# Mainboard.net
KiCad netlist of a schematic drawn in EAGLE
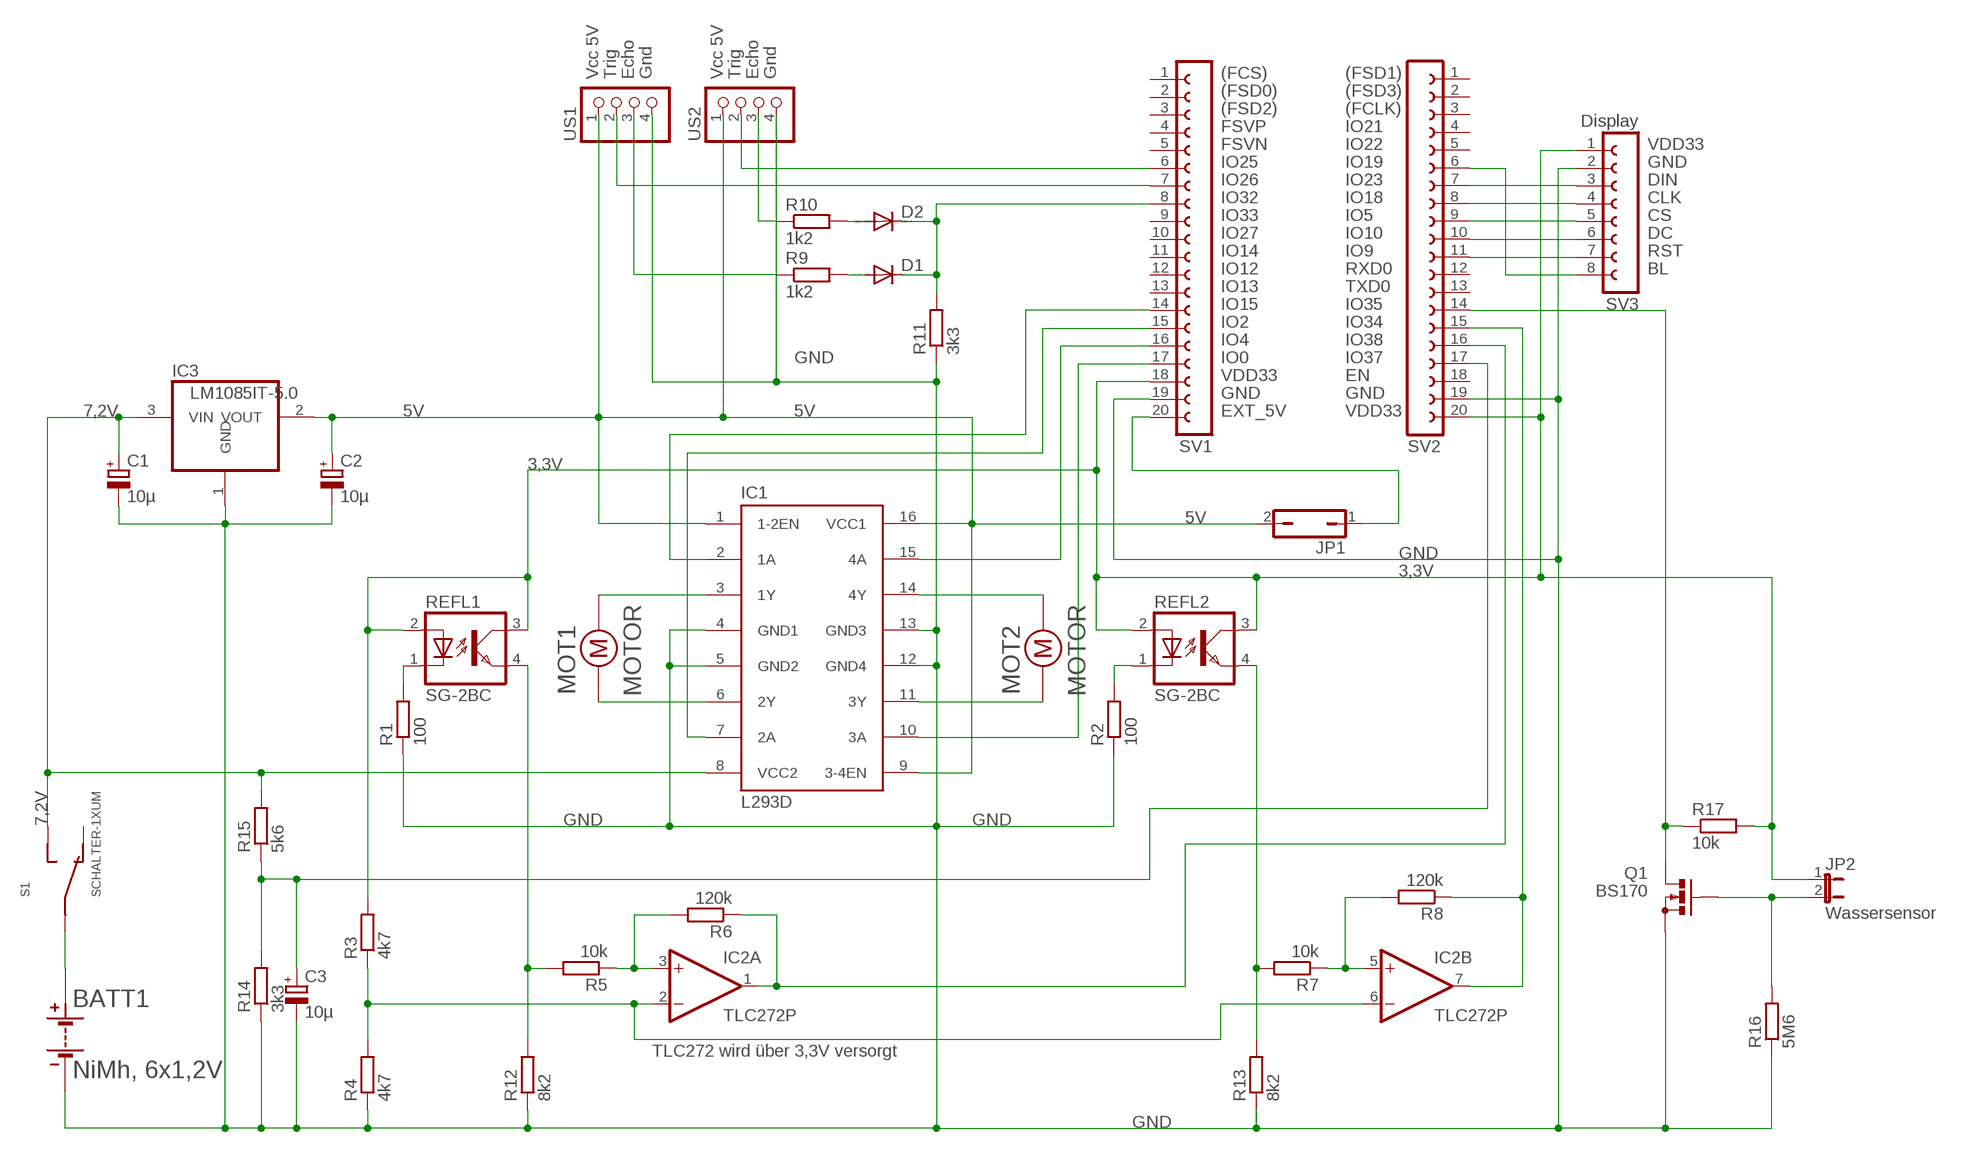
[diagram p0: schematic, sheet 1]

(export (version "E")
  (design (tool "Eeschema 10.0.6"))
  (components
    (comp (ref "BATT1")
      (value "NiMh, 6x1,2V")
      (footprint "eagle-import:DUMMY2P")
      (libsource (lib "eagle-import") (part "BATTERIEN"))
    )
    (comp (ref "C1")
      (value "10µ")
      (footprint "eagle-import:E3,5-10")
      (libsource (lib "eagle-import") (part "CPOL-EUE3.5-10"))
    )
    (comp (ref "C2")
      (value "10µ")
      (footprint "eagle-import:E3,5-10")
      (libsource (lib "eagle-import") (part "CPOL-EUE3.5-10"))
    )
    (comp (ref "C3")
      (value "10µ")
      (footprint "eagle-import:E3,5-10")
      (libsource (lib "eagle-import") (part "CPOL-EUE3.5-10"))
    )
    (comp (ref "D1")
      (value "1N4148DO35-10")
      (footprint "eagle-import:DO35-10")
      (libsource (lib "eagle-import") (part "1N4148DO35-10"))
    )
    (comp (ref "D2")
      (value "1N4148DO35-10")
      (footprint "eagle-import:DO35-10")
      (libsource (lib "eagle-import") (part "1N4148DO35-10"))
    )
    (comp (ref "IC1")
      (value "L293D")
      (footprint "eagle-import:DIL16")
      (libsource (lib "eagle-import") (part "L293D"))
    )
    (comp (ref "IC2")
      (value "TLC272P")
      (footprint "eagle-import:DIL08")
      (libsource (lib "eagle-import") (part "TLC272P"))
    )
    (comp (ref "IC3")
      (value "LM1085IT-5.0")
      (footprint "eagle-import:DD-3")
      (fields (field (name "MF") "TEXAS INSTRUMENTS") (field (name "MPN") "REG1117FAKTTT"))
      (libsource (lib "eagle-import") (part "REG1117F"))
    )
    (comp (ref "JP1")
      (value "JP1Q")
      (footprint "eagle-import:JP1")
      (libsource (lib "eagle-import") (part "JP1Q"))
    )
    (comp (ref "JP2")
      (value "Wassersensor")
      (footprint "eagle-import:JP1")
      (libsource (lib "eagle-import") (part "JP1E"))
    )
    (comp (ref "MOT1")
      (value "MOTOR")
      (footprint "eagle-import:DUMMY2P")
      (libsource (lib "eagle-import") (part "MOTOR"))
    )
    (comp (ref "MOT2")
      (value "MOTOR")
      (footprint "eagle-import:DUMMY2P")
      (libsource (lib "eagle-import") (part "MOTOR"))
    )
    (comp (ref "Q1")
      (value "BS170")
      (footprint "eagle-import:SOT54E")
      (libsource (lib "eagle-import") (part "BS170"))
    )
    (comp (ref "R1")
      (value "100")
      (footprint "eagle-import:RDH_15")
      (libsource (lib "eagle-import") (part "R-EU_RDH/15"))
    )
    (comp (ref "R2")
      (value "100")
      (footprint "eagle-import:RDH_15")
      (libsource (lib "eagle-import") (part "R-EU_RDH/15"))
    )
    (comp (ref "R3")
      (value "4k7")
      (footprint "eagle-import:RDH_15")
      (libsource (lib "eagle-import") (part "R-EU_RDH/15"))
    )
    (comp (ref "R4")
      (value "4k7")
      (footprint "eagle-import:RDH_15")
      (libsource (lib "eagle-import") (part "R-EU_RDH/15"))
    )
    (comp (ref "R5")
      (value "10k")
      (footprint "eagle-import:RDH_15")
      (libsource (lib "eagle-import") (part "R-EU_RDH/15"))
    )
    (comp (ref "R6")
      (value "120k")
      (footprint "eagle-import:RDH_15")
      (libsource (lib "eagle-import") (part "R-EU_RDH/15"))
    )
    (comp (ref "R7")
      (value "10k")
      (footprint "eagle-import:RDH_15")
      (libsource (lib "eagle-import") (part "R-EU_RDH/15"))
    )
    (comp (ref "R8")
      (value "120k")
      (footprint "eagle-import:RDH_15")
      (libsource (lib "eagle-import") (part "R-EU_RDH/15"))
    )
    (comp (ref "R9")
      (value "1k2")
      (footprint "eagle-import:RDH_15")
      (libsource (lib "eagle-import") (part "R-EU_RDH/15"))
    )
    (comp (ref "R10")
      (value "1k2")
      (footprint "eagle-import:RDH_15")
      (libsource (lib "eagle-import") (part "R-EU_RDH/15"))
    )
    (comp (ref "R11")
      (value "3k3")
      (footprint "eagle-import:RDH_15")
      (libsource (lib "eagle-import") (part "R-EU_RDH/15"))
    )
    (comp (ref "R12")
      (value "8k2")
      (footprint "eagle-import:RDH_15")
      (libsource (lib "eagle-import") (part "R-EU_RDH/15"))
    )
    (comp (ref "R13")
      (value "8k2")
      (footprint "eagle-import:RDH_15")
      (libsource (lib "eagle-import") (part "R-EU_RDH/15"))
    )
    (comp (ref "R14")
      (value "3k3")
      (footprint "eagle-import:RDH_15")
      (libsource (lib "eagle-import") (part "R-EU_RDH/15"))
    )
    (comp (ref "R15")
      (value "5k6")
      (footprint "eagle-import:RDH_15")
      (libsource (lib "eagle-import") (part "R-EU_RDH/15"))
    )
    (comp (ref "R16")
      (value "5M6")
      (footprint "eagle-import:RDH_15")
      (libsource (lib "eagle-import") (part "R-EU_RDH/15"))
    )
    (comp (ref "R17")
      (value "10k")
      (footprint "eagle-import:RDH_15")
      (libsource (lib "eagle-import") (part "R-EU_RDH/15"))
    )
    (comp (ref "REFL1")
      (value "SG-2BC")
      (footprint "eagle-import:DIL04")
      (libsource (lib "eagle-import") (part "REFLEXKOPPLERSG-2BC"))
    )
    (comp (ref "REFL2")
      (value "SG-2BC")
      (footprint "eagle-import:DIL04")
      (libsource (lib "eagle-import") (part "REFLEXKOPPLERSG-2BC"))
    )
    (comp (ref "S1")
      (value "SCHALTER-1XUM")
      (footprint "eagle-import:DUMMY3P")
      (libsource (lib "eagle-import") (part "SCHALTER-1XUM"))
    )
    (comp (ref "SV1")
      (value "FE20-1")
      (footprint "eagle-import:FE20")
      (libsource (lib "eagle-import") (part "FE20-1"))
    )
    (comp (ref "SV2")
      (value "FE20-1")
      (footprint "eagle-import:FE20")
      (libsource (lib "eagle-import") (part "FE20-1"))
    )
    (comp (ref "SV3")
      (value "Display")
      (footprint "eagle-import:FE08")
      (libsource (lib "eagle-import") (part "FE08-1"))
    )
    (comp (ref "US1")
      (value "PINHD-1X4")
      (footprint "eagle-import:1X04")
      (libsource (lib "eagle-import") (part "PINHD-1X4"))
    )
    (comp (ref "US2")
      (value "PINHD-1X4")
      (footprint "eagle-import:1X04")
      (libsource (lib "eagle-import") (part "PINHD-1X4"))
    )
  )
  (nets
    (net (code "1") (name "/3,3V") (class "Default")
      (node (ref "JP2") (pin "1") (pinfunction "1_1") (pintype "passive"))
      (node (ref "R17") (pin "2") (pinfunction "2_2") (pintype "passive"))
      (node (ref "R3") (pin "2") (pinfunction "2_2") (pintype "passive"))
      (node (ref "REFL1") (pin "2") (pinfunction "A_2") (pintype "passive"))
      (node (ref "REFL1") (pin "3") (pinfunction "COL_3") (pintype "passive"))
      (node (ref "REFL2") (pin "2") (pinfunction "A_2") (pintype "passive"))
      (node (ref "REFL2") (pin "3") (pinfunction "COL_3") (pintype "passive"))
      (node (ref "SV1") (pin "18") (pinfunction "18_18") (pintype "passive"))
      (node (ref "SV2") (pin "20") (pinfunction "20_20") (pintype "passive"))
      (node (ref "SV3") (pin "1") (pinfunction "1_1") (pintype "passive"))
    )
    (net (code "2") (name "/5V") (class "Default")
      (node (ref "C2") (pin "+") (pinfunction "+_+") (pintype "passive"))
      (node (ref "IC1") (pin "1") (pinfunction "1-2EN_1") (pintype "input"))
      (node (ref "IC1") (pin "16") (pinfunction "VCC1_16") (pintype "power_in"))
      (node (ref "IC1") (pin "9") (pinfunction "3-4EN_9") (pintype "input"))
      (node (ref "IC3") (pin "2") (pinfunction "VOUT_2") (pintype "output"))
      (node (ref "JP1") (pin "2") (pinfunction "2_2") (pintype "passive"))
      (node (ref "US1") (pin "1") (pinfunction "1_1") (pintype "passive"))
      (node (ref "US2") (pin "1") (pinfunction "1_1") (pintype "passive"))
    )
    (net (code "3") (name "/7,2V") (class "Default")
      (node (ref "C1") (pin "+") (pinfunction "+_+") (pintype "passive"))
      (node (ref "IC1") (pin "8") (pinfunction "VCC2_8") (pintype "power_in"))
      (node (ref "IC3") (pin "3") (pinfunction "VIN_3") (pintype "input"))
      (node (ref "R15") (pin "2") (pinfunction "2_2") (pintype "passive"))
      (node (ref "S1") (pin "P$2") (pinfunction "P$2_P$2") (pintype "passive"))
    )
    (net (code "4") (name "/GND") (class "Default")
      (node (ref "BATT1") (pin "P$1") (pinfunction "M_P$1") (pintype "power_in"))
      (node (ref "C1") (pin "-") (pinfunction "-_-") (pintype "passive"))
      (node (ref "C2") (pin "-") (pinfunction "-_-") (pintype "passive"))
      (node (ref "C3") (pin "-") (pinfunction "-_-") (pintype "passive"))
      (node (ref "IC1") (pin "12") (pinfunction "GND4_12") (pintype "power_in"))
      (node (ref "IC1") (pin "13") (pinfunction "GND3_13") (pintype "power_in"))
      (node (ref "IC1") (pin "4") (pinfunction "GND1_4") (pintype "power_in"))
      (node (ref "IC1") (pin "5") (pinfunction "GND2_5") (pintype "power_in"))
      (node (ref "IC3") (pin "1") (pinfunction "GND_1") (pintype "power_in"))
      (node (ref "Q1") (pin "S") (pinfunction "S_S") (pintype "passive"))
      (node (ref "R1") (pin "1") (pinfunction "1_1") (pintype "passive"))
      (node (ref "R11") (pin "1") (pinfunction "1_1") (pintype "passive"))
      (node (ref "R12") (pin "1") (pinfunction "1_1") (pintype "passive"))
      (node (ref "R13") (pin "1") (pinfunction "1_1") (pintype "passive"))
      (node (ref "R14") (pin "1") (pinfunction "1_1") (pintype "passive"))
      (node (ref "R16") (pin "1") (pinfunction "1_1") (pintype "passive"))
      (node (ref "R2") (pin "1") (pinfunction "1_1") (pintype "passive"))
      (node (ref "R4") (pin "1") (pinfunction "1_1") (pintype "passive"))
      (node (ref "SV1") (pin "19") (pinfunction "19_19") (pintype "passive"))
      (node (ref "SV2") (pin "19") (pinfunction "19_19") (pintype "passive"))
      (node (ref "SV3") (pin "2") (pinfunction "2_2") (pintype "passive"))
      (node (ref "US1") (pin "4") (pinfunction "4_4") (pintype "passive"))
      (node (ref "US2") (pin "4") (pinfunction "4_4") (pintype "passive"))
    )
    (net (code "5") (name "Net-(BATT1-P)") (class "Default")
      (node (ref "BATT1") (pin "P$2") (pinfunction "P_P$2") (pintype "power_in"))
      (node (ref "S1") (pin "P$1") (pinfunction "P$1_P$1") (pintype "passive"))
    )
    (net (code "6") (name "Net-(C3-Pad+)") (class "Default")
      (node (ref "C3") (pin "+") (pinfunction "+_+") (pintype "passive"))
      (node (ref "R14") (pin "2") (pinfunction "2_2") (pintype "passive"))
      (node (ref "R15") (pin "1") (pinfunction "1_1") (pintype "passive"))
      (node (ref "SV2") (pin "17") (pinfunction "17_17") (pintype "passive"))
    )
    (net (code "7") (name "Net-(D1-PadA)") (class "Default")
      (node (ref "D1") (pin "A") (pinfunction "A_A") (pintype "passive"))
      (node (ref "R9") (pin "2") (pinfunction "2_2") (pintype "passive"))
    )
    (net (code "8") (name "Net-(D1-PadC)") (class "Default")
      (node (ref "D1") (pin "C") (pinfunction "C_C") (pintype "passive"))
      (node (ref "D2") (pin "C") (pinfunction "C_C") (pintype "passive"))
      (node (ref "R11") (pin "2") (pinfunction "2_2") (pintype "passive"))
      (node (ref "SV1") (pin "8") (pinfunction "8_8") (pintype "passive"))
    )
    (net (code "9") (name "Net-(D2-PadA)") (class "Default")
      (node (ref "D2") (pin "A") (pinfunction "A_A") (pintype "passive"))
      (node (ref "R10") (pin "2") (pinfunction "2_2") (pintype "passive"))
    )
    (net (code "10") (name "Net-(IC1-1A)") (class "Default")
      (node (ref "IC1") (pin "2") (pinfunction "1A_2") (pintype "input"))
      (node (ref "SV1") (pin "14") (pinfunction "14_14") (pintype "passive"))
    )
    (net (code "11") (name "Net-(IC1-1Y)") (class "Default")
      (node (ref "IC1") (pin "3") (pinfunction "1Y_3") (pintype "output"))
      (node (ref "MOT1") (pin "P$2") (pinfunction "P$2_P$2") (pintype "passive"))
    )
    (net (code "12") (name "Net-(IC1-2A)") (class "Default")
      (node (ref "IC1") (pin "7") (pinfunction "2A_7") (pintype "input"))
      (node (ref "SV1") (pin "15") (pinfunction "15_15") (pintype "passive"))
    )
    (net (code "13") (name "Net-(IC1-2Y)") (class "Default")
      (node (ref "IC1") (pin "6") (pinfunction "2Y_6") (pintype "output"))
      (node (ref "MOT1") (pin "P$1") (pinfunction "P$1_P$1") (pintype "passive"))
    )
    (net (code "14") (name "Net-(IC1-3A)") (class "Default")
      (node (ref "IC1") (pin "10") (pinfunction "3A_10") (pintype "input"))
      (node (ref "SV1") (pin "17") (pinfunction "17_17") (pintype "passive"))
    )
    (net (code "15") (name "Net-(IC1-3Y)") (class "Default")
      (node (ref "IC1") (pin "11") (pinfunction "3Y_11") (pintype "output"))
      (node (ref "MOT2") (pin "P$1") (pinfunction "P$1_P$1") (pintype "passive"))
    )
    (net (code "16") (name "Net-(IC1-4A)") (class "Default")
      (node (ref "IC1") (pin "15") (pinfunction "4A_15") (pintype "input"))
      (node (ref "SV1") (pin "16") (pinfunction "16_16") (pintype "passive"))
    )
    (net (code "17") (name "Net-(IC1-4Y)") (class "Default")
      (node (ref "IC1") (pin "14") (pinfunction "4Y_14") (pintype "output"))
      (node (ref "MOT2") (pin "P$2") (pinfunction "P$2_P$2") (pintype "passive"))
    )
    (net (code "18") (name "Net-(IC2A-+IN)") (class "Default")
      (node (ref "IC2") (pin "3") (pinfunction "+IN_3") (pintype "input"))
      (node (ref "R5") (pin "1") (pinfunction "1_1") (pintype "passive"))
      (node (ref "R6") (pin "2") (pinfunction "2_2") (pintype "passive"))
    )
    (net (code "19") (name "Net-(IC2A--IN)") (class "Default")
      (node (ref "IC2") (pin "2") (pinfunction "-IN_2") (pintype "input"))
      (node (ref "IC2") (pin "6") (pinfunction "-IN_6") (pintype "input"))
      (node (ref "R3") (pin "1") (pinfunction "1_1") (pintype "passive"))
      (node (ref "R4") (pin "2") (pinfunction "2_2") (pintype "passive"))
    )
    (net (code "20") (name "Net-(IC2A-OUT)") (class "Default")
      (node (ref "IC2") (pin "1") (pinfunction "OUT_1") (pintype "output"))
      (node (ref "R6") (pin "1") (pinfunction "1_1") (pintype "passive"))
      (node (ref "SV2") (pin "16") (pinfunction "16_16") (pintype "passive"))
    )
    (net (code "21") (name "Net-(IC2B-+IN)") (class "Default")
      (node (ref "IC2") (pin "5") (pinfunction "+IN_5") (pintype "input"))
      (node (ref "R7") (pin "1") (pinfunction "1_1") (pintype "passive"))
      (node (ref "R8") (pin "2") (pinfunction "2_2") (pintype "passive"))
    )
    (net (code "22") (name "Net-(IC2B-OUT)") (class "Default")
      (node (ref "IC2") (pin "7") (pinfunction "OUT_7") (pintype "output"))
      (node (ref "R8") (pin "1") (pinfunction "1_1") (pintype "passive"))
      (node (ref "SV2") (pin "15") (pinfunction "15_15") (pintype "passive"))
    )
    (net (code "23") (name "Net-(JP1-Pad1)") (class "Default")
      (node (ref "JP1") (pin "1") (pinfunction "1_1") (pintype "passive"))
      (node (ref "SV1") (pin "20") (pinfunction "20_20") (pintype "passive"))
    )
    (net (code "24") (name "Net-(JP2-Pad2)") (class "Default")
      (node (ref "JP2") (pin "2") (pinfunction "2_2") (pintype "passive"))
      (node (ref "Q1") (pin "G") (pinfunction "G_G") (pintype "passive"))
      (node (ref "R16") (pin "2") (pinfunction "2_2") (pintype "passive"))
    )
    (net (code "25") (name "Net-(Q1-PadD)") (class "Default")
      (node (ref "Q1") (pin "D") (pinfunction "D_D") (pintype "passive"))
      (node (ref "R17") (pin "1") (pinfunction "1_1") (pintype "passive"))
      (node (ref "SV2") (pin "14") (pinfunction "14_14") (pintype "passive"))
    )
    (net (code "26") (name "Net-(R9-Pad1)") (class "Default")
      (node (ref "R9") (pin "1") (pinfunction "1_1") (pintype "passive"))
      (node (ref "US1") (pin "3") (pinfunction "3_3") (pintype "passive"))
    )
    (net (code "27") (name "Net-(R10-Pad1)") (class "Default")
      (node (ref "R10") (pin "1") (pinfunction "1_1") (pintype "passive"))
      (node (ref "US2") (pin "3") (pinfunction "3_3") (pintype "passive"))
    )
    (net (code "28") (name "Net-(REFL1-C)") (class "Default")
      (node (ref "R1") (pin "2") (pinfunction "2_2") (pintype "passive"))
      (node (ref "REFL1") (pin "1") (pinfunction "C_1") (pintype "passive"))
    )
    (net (code "29") (name "Net-(REFL1-EMIT)") (class "Default")
      (node (ref "R12") (pin "2") (pinfunction "2_2") (pintype "passive"))
      (node (ref "R5") (pin "2") (pinfunction "2_2") (pintype "passive"))
      (node (ref "REFL1") (pin "4") (pinfunction "EMIT_4") (pintype "passive"))
    )
    (net (code "30") (name "Net-(REFL2-C)") (class "Default")
      (node (ref "R2") (pin "2") (pinfunction "2_2") (pintype "passive"))
      (node (ref "REFL2") (pin "1") (pinfunction "C_1") (pintype "passive"))
    )
    (net (code "31") (name "Net-(REFL2-EMIT)") (class "Default")
      (node (ref "R13") (pin "2") (pinfunction "2_2") (pintype "passive"))
      (node (ref "R7") (pin "2") (pinfunction "2_2") (pintype "passive"))
      (node (ref "REFL2") (pin "4") (pinfunction "EMIT_4") (pintype "passive"))
    )
    (net (code "32") (name "Net-(SV1-Pad6)") (class "Default")
      (node (ref "SV1") (pin "6") (pinfunction "6_6") (pintype "passive"))
      (node (ref "US2") (pin "2") (pinfunction "2_2") (pintype "passive"))
    )
    (net (code "33") (name "Net-(SV1-Pad7)") (class "Default")
      (node (ref "SV1") (pin "7") (pinfunction "7_7") (pintype "passive"))
      (node (ref "US1") (pin "2") (pinfunction "2_2") (pintype "passive"))
    )
    (net (code "34") (name "Net-(SV2-Pad6)") (class "Default")
      (node (ref "SV2") (pin "6") (pinfunction "6_6") (pintype "passive"))
      (node (ref "SV3") (pin "8") (pinfunction "8_8") (pintype "passive"))
    )
    (net (code "35") (name "Net-(SV2-Pad7)") (class "Default")
      (node (ref "SV2") (pin "7") (pinfunction "7_7") (pintype "passive"))
      (node (ref "SV3") (pin "3") (pinfunction "3_3") (pintype "passive"))
    )
    (net (code "36") (name "Net-(SV2-Pad8)") (class "Default")
      (node (ref "SV2") (pin "8") (pinfunction "8_8") (pintype "passive"))
      (node (ref "SV3") (pin "4") (pinfunction "4_4") (pintype "passive"))
    )
    (net (code "37") (name "Net-(SV2-Pad9)") (class "Default")
      (node (ref "SV2") (pin "9") (pinfunction "9_9") (pintype "passive"))
      (node (ref "SV3") (pin "5") (pinfunction "5_5") (pintype "passive"))
    )
    (net (code "38") (name "Net-(SV2-Pad10)") (class "Default")
      (node (ref "SV2") (pin "10") (pinfunction "10_10") (pintype "passive"))
      (node (ref "SV3") (pin "6") (pinfunction "6_6") (pintype "passive"))
    )
    (net (code "39") (name "Net-(SV2-Pad11)") (class "Default")
      (node (ref "SV2") (pin "11") (pinfunction "11_11") (pintype "passive"))
      (node (ref "SV3") (pin "7") (pinfunction "7_7") (pintype "passive"))
    )
    (net (code "40") (name "unconnected-(S1-PadP$3)") (class "Default")
      (node (ref "S1") (pin "P$3") (pinfunction "P$3_P$3") (pintype "passive"))
    )
    (net (code "41") (name "unconnected-(SV1-Pad1)") (class "Default")
      (node (ref "SV1") (pin "1") (pinfunction "1_1") (pintype "passive"))
    )
    (net (code "42") (name "unconnected-(SV1-Pad2)") (class "Default")
      (node (ref "SV1") (pin "2") (pinfunction "2_2") (pintype "passive"))
    )
    (net (code "43") (name "unconnected-(SV1-Pad3)") (class "Default")
      (node (ref "SV1") (pin "3") (pinfunction "3_3") (pintype "passive"))
    )
    (net (code "44") (name "unconnected-(SV1-Pad4)") (class "Default")
      (node (ref "SV1") (pin "4") (pinfunction "4_4") (pintype "passive"))
    )
    (net (code "45") (name "unconnected-(SV1-Pad5)") (class "Default")
      (node (ref "SV1") (pin "5") (pinfunction "5_5") (pintype "passive"))
    )
    (net (code "46") (name "unconnected-(SV1-Pad9)") (class "Default")
      (node (ref "SV1") (pin "9") (pinfunction "9_9") (pintype "passive"))
    )
    (net (code "47") (name "unconnected-(SV1-Pad10)") (class "Default")
      (node (ref "SV1") (pin "10") (pinfunction "10_10") (pintype "passive"))
    )
    (net (code "48") (name "unconnected-(SV1-Pad11)") (class "Default")
      (node (ref "SV1") (pin "11") (pinfunction "11_11") (pintype "passive"))
    )
    (net (code "49") (name "unconnected-(SV1-Pad12)") (class "Default")
      (node (ref "SV1") (pin "12") (pinfunction "12_12") (pintype "passive"))
    )
    (net (code "50") (name "unconnected-(SV1-Pad13)") (class "Default")
      (node (ref "SV1") (pin "13") (pinfunction "13_13") (pintype "passive"))
    )
    (net (code "51") (name "unconnected-(SV2-Pad1)") (class "Default")
      (node (ref "SV2") (pin "1") (pinfunction "1_1") (pintype "passive"))
    )
    (net (code "52") (name "unconnected-(SV2-Pad2)") (class "Default")
      (node (ref "SV2") (pin "2") (pinfunction "2_2") (pintype "passive"))
    )
    (net (code "53") (name "unconnected-(SV2-Pad3)") (class "Default")
      (node (ref "SV2") (pin "3") (pinfunction "3_3") (pintype "passive"))
    )
    (net (code "54") (name "unconnected-(SV2-Pad4)") (class "Default")
      (node (ref "SV2") (pin "4") (pinfunction "4_4") (pintype "passive"))
    )
    (net (code "55") (name "unconnected-(SV2-Pad5)") (class "Default")
      (node (ref "SV2") (pin "5") (pinfunction "5_5") (pintype "passive"))
    )
    (net (code "56") (name "unconnected-(SV2-Pad12)") (class "Default")
      (node (ref "SV2") (pin "12") (pinfunction "12_12") (pintype "passive"))
    )
    (net (code "57") (name "unconnected-(SV2-Pad13)") (class "Default")
      (node (ref "SV2") (pin "13") (pinfunction "13_13") (pintype "passive"))
    )
    (net (code "58") (name "unconnected-(SV2-Pad18)") (class "Default")
      (node (ref "SV2") (pin "18") (pinfunction "18_18") (pintype "passive"))
    )
  )
)
